# EG_robot.net
KiCad netlist of a schematic drawn in Altium Designer
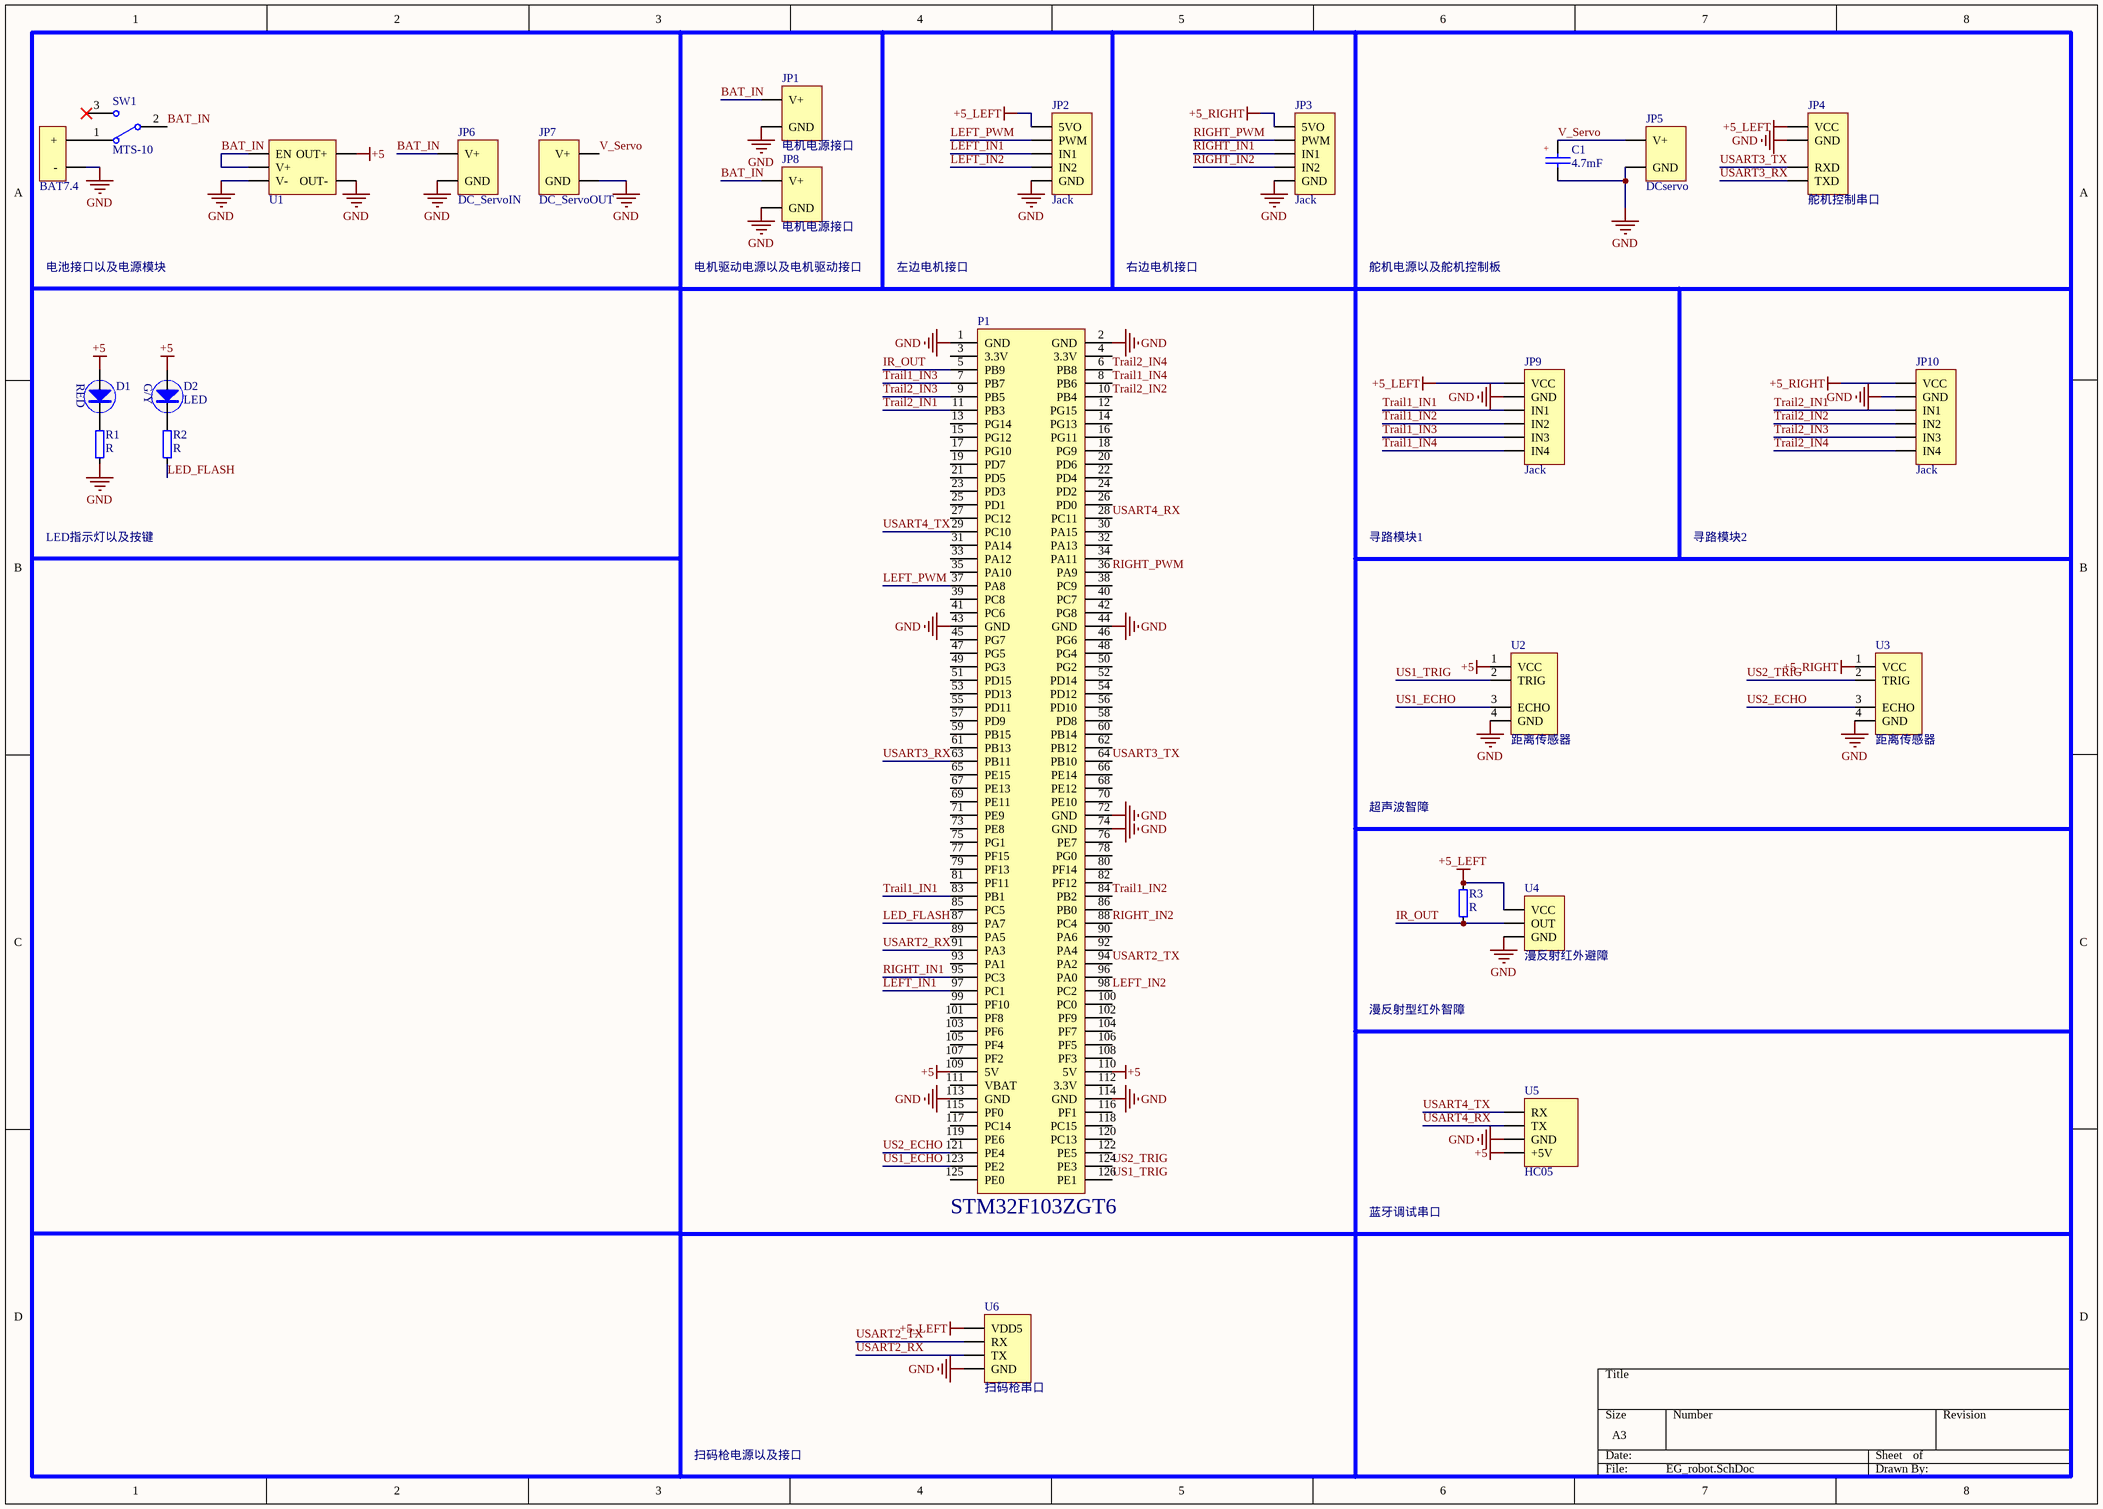
[diagram p0: EG_robot.SchDoc]

(export (version "E")
  (design (tool "Eeschema 10.0.6"))
  (components
    (comp (ref "BAT1") (value "BAT7.4") (footprint "POWER") (libsource (lib "EG_robot") (part "POWER_COM")))
    (comp (ref "C1")
      (value "4.7mF")
      (footprint "CAP 7.5*16*31.5 - BK")
      (description "7.6*16*35")
      (libsource (lib "EG_robot") (part "CAP_DIP7.6*16.35"))
    )
    (comp (ref "D1")
      (value "1206LED")
      (footprint "LED 1206R")
      (description "LED")
      (libsource (lib "EG_robot") (part "LED_RED"))
    )
    (comp (ref "D2") (value "LED") (footprint "LED 1206Y") (libsource (lib "EG_robot") (part "LED_GY")))
    (comp (ref "JP1")
      (value "电机电源接口")
      (footprint "SMALL_POWER_JACK")
      (libsource (lib "EG_robot") (part "DC_moto"))
    )
    (comp (ref "JP2")
      (value "Jack")
      (footprint "XH2.54-LI-5P")
      (description "White Small")
      (libsource (lib "EG_robot") (part "Moto"))
    )
    (comp (ref "JP3")
      (value "Jack")
      (footprint "XH2.54-LI-5P")
      (description "White Small")
      (libsource (lib "EG_robot") (part "Moto"))
    )
    (comp (ref "JP4")
      (value "舵机控制串口")
      (footprint "XH2.54-LI-4P")
      (libsource (lib "EG_robot") (part "舵机控制串口"))
    )
    (comp (ref "JP5")
      (value "DCservo")
      (footprint "SMALL_POWER_JACK")
      (description "Power input for Servo Control Board")
      (libsource (lib "EG_robot") (part "DCservo"))
    )
    (comp (ref "JP6")
      (value "DC_ServoIN")
      (footprint "SMALL_POWER_JACK")
      (libsource (lib "EG_robot") (part "DC_ServoIN"))
    )
    (comp (ref "JP7")
      (value "DC_ServoOUT")
      (footprint "SMALL_POWER_JACK")
      (libsource (lib "EG_robot") (part "DC_ServoOUT"))
    )
    (comp (ref "JP8")
      (value "电机电源接口")
      (footprint "SMALL_POWER_JACK")
      (libsource (lib "EG_robot") (part "DC_moto"))
    )
    (comp (ref "JP9")
      (value "Jack")
      (footprint "XH2.54-LI-6P")
      (description "White Small")
      (libsource (lib "EG_robot") (part "循迹模块"))
    )
    (comp (ref "JP10")
      (value "Jack")
      (footprint "XH2.54-LI-6P")
      (description "White Small")
      (libsource (lib "EG_robot") (part "循迹模块"))
    )
    (comp (ref "P1")
      (value "Header 63X2")
      (footprint "YD最小系统版接口")
      (description "Header, 126-Pin, Dual row")
      (fields (field (name "PUBLISHER") "Altium Limited"))
      (libsource (lib "EG_robot") (part "Header 63X2"))
    )
    (comp (ref "R1")
      (value "R")
      (footprint "1206R")
      (description "SMT_1206")
      (libsource (lib "EG_robot") (part "SMT1206"))
    )
    (comp (ref "R2")
      (value "R")
      (footprint "1206R")
      (description "SMT_1206")
      (libsource (lib "EG_robot") (part "SMT1206"))
    )
    (comp (ref "R3")
      (value "R")
      (footprint "1206R")
      (description "SMT_1206")
      (libsource (lib "EG_robot") (part "SMT1206"))
    )
    (comp (ref "SW1")
      (value "MTS-10")
      (footprint "MTS-10x")
      (description "MTS-10 series")
      (libsource (lib "EG_robot") (part "MTS_10-DIP"))
    )
    (comp (ref "U1")
      (value "DC5V")
      (footprint "DC5V_BUCKBOOST")
      (description "DC5V Fixed Buck-Boost voltage regulator")
      (libsource (lib "EG_robot") (part "DC5V"))
    )
    (comp (ref "U2")
      (value "距离传感器")
      (footprint "XH2.54-LI-4P")
      (description "Ultrasonic distant detector")
      (libsource (lib "EG_robot") (part "HCSR04"))
    )
    (comp (ref "U3")
      (value "距离传感器")
      (footprint "XH2.54-LI-4P")
      (description "Ultrasonic distant detector")
      (libsource (lib "EG_robot") (part "HCSR04"))
    )
    (comp (ref "U4") (value "漫反射红外避障") (footprint "XH2.54-LI-3P") (libsource (lib "EG_robot") (part "红外避障")))
    (comp (ref "U5") (value "HC05") (footprint "XH2.54-LI-4P") (libsource (lib "EG_robot") (part "HC05")))
    (comp (ref "U6") (value "扫码枪串口") (footprint "XH2.54-LI-4P") (libsource (lib "EG_robot") (part "扫码枪")))
  )
  (nets
    (net (code "1") (name "+5") (class "Default")
      (node (ref "D1") (pin "1") (pinfunction "A_1") (pintype "passive"))
      (node (ref "D2") (pin "1") (pinfunction "A_1") (pintype "passive"))
      (node (ref "P1") (pin "109") (pinfunction "5V_109") (pintype "passive"))
      (node (ref "P1") (pin "110") (pinfunction "5V_110") (pintype "passive"))
      (node (ref "U1") (pin "2") (pinfunction "OUT+_2") (pintype "passive"))
      (node (ref "U2") (pin "1") (pinfunction "VCC_1") (pintype "passive"))
      (node (ref "U5") (pin "4") (pinfunction "+5V_4") (pintype "passive"))
    )
    (net (code "2") (name "+5_LEFT") (class "Default")
      (node (ref "JP2") (pin "1") (pinfunction "5VO_1") (pintype "passive"))
      (node (ref "JP4") (pin "1") (pinfunction "VCC_1") (pintype "passive"))
      (node (ref "JP9") (pin "1") (pinfunction "VCC_1") (pintype "passive"))
      (node (ref "R3") (pin "2") (pinfunction "2_2") (pintype "passive"))
      (node (ref "U4") (pin "1") (pinfunction "VCC_1") (pintype "passive"))
      (node (ref "U6") (pin "1") (pinfunction "VDD5_1") (pintype "passive"))
    )
    (net (code "3") (name "+5_RIGHT") (class "Default")
      (node (ref "JP10") (pin "1") (pinfunction "VCC_1") (pintype "passive"))
      (node (ref "JP3") (pin "1") (pinfunction "5VO_1") (pintype "passive"))
      (node (ref "U3") (pin "1") (pinfunction "VCC_1") (pintype "passive"))
    )
    (net (code "4") (name "/BAT_IN") (class "Default")
      (node (ref "JP1") (pin "1") (pinfunction "V+_1") (pintype "passive"))
      (node (ref "JP6") (pin "1") (pinfunction "V+_1") (pintype "passive"))
      (node (ref "JP8") (pin "1") (pinfunction "V+_1") (pintype "passive"))
      (node (ref "SW1") (pin "2") (pinfunction "2_2") (pintype "passive"))
      (node (ref "U1") (pin "3") (pinfunction "EN_3") (pintype "passive"))
      (node (ref "U1") (pin "4") (pinfunction "V+_4") (pintype "passive"))
    )
    (net (code "5") (name "/IR_OUT") (class "Default")
      (node (ref "P1") (pin "5") (pinfunction "PB9_5") (pintype "passive"))
      (node (ref "R3") (pin "1") (pinfunction "1_1") (pintype "passive"))
      (node (ref "U4") (pin "2") (pinfunction "OUT_2") (pintype "passive"))
    )
    (net (code "6") (name "/LED_FLASH") (class "Default")
      (node (ref "P1") (pin "87") (pinfunction "PA7_87") (pintype "passive"))
      (node (ref "R2") (pin "1") (pinfunction "1_1") (pintype "passive"))
    )
    (net (code "7") (name "/LEFT_IN1") (class "Default")
      (node (ref "JP2") (pin "3") (pinfunction "IN1_3") (pintype "passive"))
      (node (ref "P1") (pin "97") (pinfunction "PC1_97") (pintype "passive"))
    )
    (net (code "8") (name "/LEFT_IN2") (class "Default")
      (node (ref "JP2") (pin "4") (pinfunction "IN2_4") (pintype "passive"))
      (node (ref "P1") (pin "98") (pinfunction "PC2_98") (pintype "passive"))
    )
    (net (code "9") (name "/LEFT_PWM") (class "Default")
      (node (ref "JP2") (pin "2") (pinfunction "PWM_2") (pintype "passive"))
      (node (ref "P1") (pin "37") (pinfunction "PA8_37") (pintype "passive"))
    )
    (net (code "10") (name "/RIGHT_IN1") (class "Default")
      (node (ref "JP3") (pin "3") (pinfunction "IN1_3") (pintype "passive"))
      (node (ref "P1") (pin "95") (pinfunction "PC3_95") (pintype "passive"))
    )
    (net (code "11") (name "/RIGHT_IN2") (class "Default")
      (node (ref "JP3") (pin "4") (pinfunction "IN2_4") (pintype "passive"))
      (node (ref "P1") (pin "88") (pinfunction "PC4_88") (pintype "passive"))
    )
    (net (code "12") (name "/RIGHT_PWM") (class "Default")
      (node (ref "JP3") (pin "2") (pinfunction "PWM_2") (pintype "passive"))
      (node (ref "P1") (pin "36") (pinfunction "PA9_36") (pintype "passive"))
    )
    (net (code "13") (name "/Trail1_IN1") (class "Default")
      (node (ref "JP9") (pin "3") (pinfunction "IN1_3") (pintype "passive"))
      (node (ref "P1") (pin "83") (pinfunction "PB1_83") (pintype "passive"))
    )
    (net (code "14") (name "/Trail1_IN2") (class "Default")
      (node (ref "JP9") (pin "4") (pinfunction "IN2_4") (pintype "passive"))
      (node (ref "P1") (pin "84") (pinfunction "PB2_84") (pintype "passive"))
    )
    (net (code "15") (name "/Trail1_IN3") (class "Default")
      (node (ref "JP9") (pin "5") (pinfunction "IN3_5") (pintype "passive"))
      (node (ref "P1") (pin "7") (pinfunction "PB7_7") (pintype "passive"))
    )
    (net (code "16") (name "/Trail1_IN4") (class "Default")
      (node (ref "JP9") (pin "6") (pinfunction "IN4_6") (pintype "passive"))
      (node (ref "P1") (pin "8") (pinfunction "PB6_8") (pintype "passive"))
    )
    (net (code "17") (name "/Trail2_IN1") (class "Default")
      (node (ref "JP10") (pin "3") (pinfunction "IN1_3") (pintype "passive"))
      (node (ref "P1") (pin "11") (pinfunction "PB3_11") (pintype "passive"))
    )
    (net (code "18") (name "/Trail2_IN2") (class "Default")
      (node (ref "JP10") (pin "4") (pinfunction "IN2_4") (pintype "passive"))
      (node (ref "P1") (pin "10") (pinfunction "PB4_10") (pintype "passive"))
    )
    (net (code "19") (name "/Trail2_IN3") (class "Default")
      (node (ref "JP10") (pin "5") (pinfunction "IN3_5") (pintype "passive"))
      (node (ref "P1") (pin "9") (pinfunction "PB5_9") (pintype "passive"))
    )
    (net (code "20") (name "/Trail2_IN4") (class "Default")
      (node (ref "JP10") (pin "6") (pinfunction "IN4_6") (pintype "passive"))
      (node (ref "P1") (pin "6") (pinfunction "PB8_6") (pintype "passive"))
    )
    (net (code "21") (name "/US1_ECHO") (class "Default")
      (node (ref "P1") (pin "123") (pinfunction "PE2_123") (pintype "passive"))
      (node (ref "U2") (pin "3") (pinfunction "ECHO_3") (pintype "passive"))
    )
    (net (code "22") (name "/US1_TRIG") (class "Default")
      (node (ref "P1") (pin "126") (pinfunction "PE1_126") (pintype "passive"))
      (node (ref "U2") (pin "2") (pinfunction "TRIG_2") (pintype "passive"))
    )
    (net (code "23") (name "/US2_ECHO") (class "Default")
      (node (ref "P1") (pin "121") (pinfunction "PE4_121") (pintype "passive"))
      (node (ref "U3") (pin "3") (pinfunction "ECHO_3") (pintype "passive"))
    )
    (net (code "24") (name "/US2_TRIG") (class "Default")
      (node (ref "P1") (pin "124") (pinfunction "PE3_124") (pintype "passive"))
      (node (ref "U3") (pin "2") (pinfunction "TRIG_2") (pintype "passive"))
    )
    (net (code "25") (name "/USART2_RX") (class "Default")
      (node (ref "P1") (pin "91") (pinfunction "PA3_91") (pintype "passive"))
      (node (ref "U6") (pin "3") (pinfunction "TX_3") (pintype "passive"))
    )
    (net (code "26") (name "/USART2_TX") (class "Default")
      (node (ref "P1") (pin "94") (pinfunction "PA2_94") (pintype "passive"))
      (node (ref "U6") (pin "2") (pinfunction "RX_2") (pintype "passive"))
    )
    (net (code "27") (name "/USART3_RX") (class "Default")
      (node (ref "JP4") (pin "4") (pinfunction "TXD_4") (pintype "passive"))
      (node (ref "P1") (pin "63") (pinfunction "PB11_63") (pintype "passive"))
    )
    (net (code "28") (name "/USART3_TX") (class "Default")
      (node (ref "JP4") (pin "3") (pinfunction "RXD_3") (pintype "passive"))
      (node (ref "P1") (pin "64") (pinfunction "PB10_64") (pintype "passive"))
    )
    (net (code "29") (name "/USART4_RX") (class "Default")
      (node (ref "P1") (pin "28") (pinfunction "PC11_28") (pintype "passive"))
      (node (ref "U5") (pin "2") (pinfunction "TX_2") (pintype "passive"))
    )
    (net (code "30") (name "/USART4_TX") (class "Default")
      (node (ref "P1") (pin "29") (pinfunction "PC10_29") (pintype "passive"))
      (node (ref "U5") (pin "1") (pinfunction "RX_1") (pintype "passive"))
    )
    (net (code "31") (name "/V_Servo") (class "Default")
      (node (ref "C1") (pin "1") (pinfunction "1_1") (pintype "passive"))
      (node (ref "JP5") (pin "1") (pinfunction "V+_1") (pintype "passive"))
      (node (ref "JP7") (pin "1") (pinfunction "V+_1") (pintype "passive"))
    )
    (net (code "32") (name "GND") (class "Default")
      (node (ref "BAT1") (pin "2") (pinfunction "-_2") (pintype "passive"))
      (node (ref "C1") (pin "2") (pinfunction "2_2") (pintype "passive"))
      (node (ref "JP1") (pin "2") (pinfunction "GND_2") (pintype "passive"))
      (node (ref "JP10") (pin "2") (pinfunction "GND_2") (pintype "passive"))
      (node (ref "JP2") (pin "5") (pinfunction "GND_5") (pintype "passive"))
      (node (ref "JP3") (pin "5") (pinfunction "GND_5") (pintype "passive"))
      (node (ref "JP4") (pin "2") (pinfunction "GND_2") (pintype "passive"))
      (node (ref "JP5") (pin "2") (pinfunction "GND_2") (pintype "passive"))
      (node (ref "JP6") (pin "2") (pinfunction "GND_2") (pintype "passive"))
      (node (ref "JP7") (pin "2") (pinfunction "GND_2") (pintype "passive"))
      (node (ref "JP8") (pin "2") (pinfunction "GND_2") (pintype "passive"))
      (node (ref "JP9") (pin "2") (pinfunction "GND_2") (pintype "passive"))
      (node (ref "P1") (pin "1") (pinfunction "GND_1") (pintype "passive"))
      (node (ref "P1") (pin "113") (pinfunction "GND_113") (pintype "passive"))
      (node (ref "P1") (pin "114") (pinfunction "GND_114") (pintype "passive"))
      (node (ref "P1") (pin "2") (pinfunction "GND_2") (pintype "passive"))
      (node (ref "P1") (pin "43") (pinfunction "GND_43") (pintype "passive"))
      (node (ref "P1") (pin "44") (pinfunction "GND_44") (pintype "passive"))
      (node (ref "P1") (pin "72") (pinfunction "GND_72") (pintype "passive"))
      (node (ref "P1") (pin "74") (pinfunction "GND_74") (pintype "passive"))
      (node (ref "R1") (pin "1") (pinfunction "1_1") (pintype "passive"))
      (node (ref "U1") (pin "1") (pinfunction "OUT-_1") (pintype "passive"))
      (node (ref "U1") (pin "5") (pinfunction "V-_5") (pintype "passive"))
      (node (ref "U2") (pin "4") (pinfunction "GND_4") (pintype "passive"))
      (node (ref "U3") (pin "4") (pinfunction "GND_4") (pintype "passive"))
      (node (ref "U4") (pin "3") (pinfunction "GND_3") (pintype "passive"))
      (node (ref "U5") (pin "3") (pinfunction "GND_3") (pintype "passive"))
      (node (ref "U6") (pin "4") (pinfunction "GND_4") (pintype "passive"))
    )
    (net (code "33") (name "Net-(BAT1-+)") (class "Default")
      (node (ref "BAT1") (pin "1") (pinfunction "+_1") (pintype "passive"))
      (node (ref "SW1") (pin "1") (pinfunction "1_1") (pintype "passive"))
    )
    (net (code "34") (name "Net-(D1-K)") (class "Default")
      (node (ref "D1") (pin "2") (pinfunction "K_2") (pintype "passive"))
      (node (ref "R1") (pin "2") (pinfunction "2_2") (pintype "passive"))
    )
    (net (code "35") (name "Net-(D2-K)") (class "Default")
      (node (ref "D2") (pin "2") (pinfunction "K_2") (pintype "passive"))
      (node (ref "R2") (pin "2") (pinfunction "2_2") (pintype "passive"))
    )
    (net (code "36") (name "unconnected-(P1-3.3V-Pad3)") (class "Default")
      (node (ref "P1") (pin "3") (pinfunction "3.3V_3") (pintype "passive"))
    )
    (net (code "37") (name "unconnected-(P1-3.3V-Pad4)") (class "Default")
      (node (ref "P1") (pin "4") (pinfunction "3.3V_4") (pintype "passive"))
    )
    (net (code "38") (name "unconnected-(P1-3.3V-Pad112)") (class "Default")
      (node (ref "P1") (pin "112") (pinfunction "3.3V_112") (pintype "passive"))
    )
    (net (code "39") (name "unconnected-(P1-PA0-Pad96)") (class "Default")
      (node (ref "P1") (pin "96") (pinfunction "PA0_96") (pintype "passive"))
    )
    (net (code "40") (name "unconnected-(P1-PA1-Pad93)") (class "Default")
      (node (ref "P1") (pin "93") (pinfunction "PA1_93") (pintype "passive"))
    )
    (net (code "41") (name "unconnected-(P1-PA4-Pad92)") (class "Default")
      (node (ref "P1") (pin "92") (pinfunction "PA4_92") (pintype "passive"))
    )
    (net (code "42") (name "unconnected-(P1-PA5-Pad89)") (class "Default")
      (node (ref "P1") (pin "89") (pinfunction "PA5_89") (pintype "passive"))
    )
    (net (code "43") (name "unconnected-(P1-PA6-Pad90)") (class "Default")
      (node (ref "P1") (pin "90") (pinfunction "PA6_90") (pintype "passive"))
    )
    (net (code "44") (name "unconnected-(P1-PA10-Pad35)") (class "Default")
      (node (ref "P1") (pin "35") (pinfunction "PA10_35") (pintype "passive"))
    )
    (net (code "45") (name "unconnected-(P1-PA11-Pad34)") (class "Default")
      (node (ref "P1") (pin "34") (pinfunction "PA11_34") (pintype "passive"))
    )
    (net (code "46") (name "unconnected-(P1-PA12-Pad33)") (class "Default")
      (node (ref "P1") (pin "33") (pinfunction "PA12_33") (pintype "passive"))
    )
    (net (code "47") (name "unconnected-(P1-PA13-Pad32)") (class "Default")
      (node (ref "P1") (pin "32") (pinfunction "PA13_32") (pintype "passive"))
    )
    (net (code "48") (name "unconnected-(P1-PA14-Pad31)") (class "Default")
      (node (ref "P1") (pin "31") (pinfunction "PA14_31") (pintype "passive"))
    )
    (net (code "49") (name "unconnected-(P1-PA15-Pad30)") (class "Default")
      (node (ref "P1") (pin "30") (pinfunction "PA15_30") (pintype "passive"))
    )
    (net (code "50") (name "unconnected-(P1-PB0-Pad86)") (class "Default")
      (node (ref "P1") (pin "86") (pinfunction "PB0_86") (pintype "passive"))
    )
    (net (code "51") (name "unconnected-(P1-PB12-Pad62)") (class "Default")
      (node (ref "P1") (pin "62") (pinfunction "PB12_62") (pintype "passive"))
    )
    (net (code "52") (name "unconnected-(P1-PB13-Pad61)") (class "Default")
      (node (ref "P1") (pin "61") (pinfunction "PB13_61") (pintype "passive"))
    )
    (net (code "53") (name "unconnected-(P1-PB14-Pad60)") (class "Default")
      (node (ref "P1") (pin "60") (pinfunction "PB14_60") (pintype "passive"))
    )
    (net (code "54") (name "unconnected-(P1-PB15-Pad59)") (class "Default")
      (node (ref "P1") (pin "59") (pinfunction "PB15_59") (pintype "passive"))
    )
    (net (code "55") (name "unconnected-(P1-PC0-Pad100)") (class "Default")
      (node (ref "P1") (pin "100") (pinfunction "PC0_100") (pintype "passive"))
    )
    (net (code "56") (name "unconnected-(P1-PC5-Pad85)") (class "Default")
      (node (ref "P1") (pin "85") (pinfunction "PC5_85") (pintype "passive"))
    )
    (net (code "57") (name "unconnected-(P1-PC6-Pad41)") (class "Default")
      (node (ref "P1") (pin "41") (pinfunction "PC6_41") (pintype "passive"))
    )
    (net (code "58") (name "unconnected-(P1-PC7-Pad40)") (class "Default")
      (node (ref "P1") (pin "40") (pinfunction "PC7_40") (pintype "passive"))
    )
    (net (code "59") (name "unconnected-(P1-PC8-Pad39)") (class "Default")
      (node (ref "P1") (pin "39") (pinfunction "PC8_39") (pintype "passive"))
    )
    (net (code "60") (name "unconnected-(P1-PC9-Pad38)") (class "Default")
      (node (ref "P1") (pin "38") (pinfunction "PC9_38") (pintype "passive"))
    )
    (net (code "61") (name "unconnected-(P1-PC12-Pad27)") (class "Default")
      (node (ref "P1") (pin "27") (pinfunction "PC12_27") (pintype "passive"))
    )
    (net (code "62") (name "unconnected-(P1-PC13-Pad120)") (class "Default")
      (node (ref "P1") (pin "120") (pinfunction "PC13_120") (pintype "passive"))
    )
    (net (code "63") (name "unconnected-(P1-PC14-Pad117)") (class "Default")
      (node (ref "P1") (pin "117") (pinfunction "PC14_117") (pintype "passive"))
    )
    (net (code "64") (name "unconnected-(P1-PC15-Pad118)") (class "Default")
      (node (ref "P1") (pin "118") (pinfunction "PC15_118") (pintype "passive"))
    )
    (net (code "65") (name "unconnected-(P1-PD0-Pad26)") (class "Default")
      (node (ref "P1") (pin "26") (pinfunction "PD0_26") (pintype "passive"))
    )
    (net (code "66") (name "unconnected-(P1-PD1-Pad25)") (class "Default")
      (node (ref "P1") (pin "25") (pinfunction "PD1_25") (pintype "passive"))
    )
    (net (code "67") (name "unconnected-(P1-PD2-Pad24)") (class "Default")
      (node (ref "P1") (pin "24") (pinfunction "PD2_24") (pintype "passive"))
    )
    (net (code "68") (name "unconnected-(P1-PD3-Pad23)") (class "Default")
      (node (ref "P1") (pin "23") (pinfunction "PD3_23") (pintype "passive"))
    )
    (net (code "69") (name "unconnected-(P1-PD4-Pad22)") (class "Default")
      (node (ref "P1") (pin "22") (pinfunction "PD4_22") (pintype "passive"))
    )
    (net (code "70") (name "unconnected-(P1-PD5-Pad21)") (class "Default")
      (node (ref "P1") (pin "21") (pinfunction "PD5_21") (pintype "passive"))
    )
    (net (code "71") (name "unconnected-(P1-PD6-Pad20)") (class "Default")
      (node (ref "P1") (pin "20") (pinfunction "PD6_20") (pintype "passive"))
    )
    (net (code "72") (name "unconnected-(P1-PD7-Pad19)") (class "Default")
      (node (ref "P1") (pin "19") (pinfunction "PD7_19") (pintype "passive"))
    )
    (net (code "73") (name "unconnected-(P1-PD8-Pad58)") (class "Default")
      (node (ref "P1") (pin "58") (pinfunction "PD8_58") (pintype "passive"))
    )
    (net (code "74") (name "unconnected-(P1-PD9-Pad57)") (class "Default")
      (node (ref "P1") (pin "57") (pinfunction "PD9_57") (pintype "passive"))
    )
    (net (code "75") (name "unconnected-(P1-PD10-Pad56)") (class "Default")
      (node (ref "P1") (pin "56") (pinfunction "PD10_56") (pintype "passive"))
    )
    (net (code "76") (name "unconnected-(P1-PD11-Pad55)") (class "Default")
      (node (ref "P1") (pin "55") (pinfunction "PD11_55") (pintype "passive"))
    )
    (net (code "77") (name "unconnected-(P1-PD12-Pad54)") (class "Default")
      (node (ref "P1") (pin "54") (pinfunction "PD12_54") (pintype "passive"))
    )
    (net (code "78") (name "unconnected-(P1-PD13-Pad53)") (class "Default")
      (node (ref "P1") (pin "53") (pinfunction "PD13_53") (pintype "passive"))
    )
    (net (code "79") (name "unconnected-(P1-PD14-Pad52)") (class "Default")
      (node (ref "P1") (pin "52") (pinfunction "PD14_52") (pintype "passive"))
    )
    (net (code "80") (name "unconnected-(P1-PD15-Pad51)") (class "Default")
      (node (ref "P1") (pin "51") (pinfunction "PD15_51") (pintype "passive"))
    )
    (net (code "81") (name "unconnected-(P1-PE0-Pad125)") (class "Default")
      (node (ref "P1") (pin "125") (pinfunction "PE0_125") (pintype "passive"))
    )
    (net (code "82") (name "unconnected-(P1-PE5-Pad122)") (class "Default")
      (node (ref "P1") (pin "122") (pinfunction "PE5_122") (pintype "passive"))
    )
    (net (code "83") (name "unconnected-(P1-PE6-Pad119)") (class "Default")
      (node (ref "P1") (pin "119") (pinfunction "PE6_119") (pintype "passive"))
    )
    (net (code "84") (name "unconnected-(P1-PE7-Pad76)") (class "Default")
      (node (ref "P1") (pin "76") (pinfunction "PE7_76") (pintype "passive"))
    )
    (net (code "85") (name "unconnected-(P1-PE8-Pad73)") (class "Default")
      (node (ref "P1") (pin "73") (pinfunction "PE8_73") (pintype "passive"))
    )
    (net (code "86") (name "unconnected-(P1-PE9-Pad71)") (class "Default")
      (node (ref "P1") (pin "71") (pinfunction "PE9_71") (pintype "passive"))
    )
    (net (code "87") (name "unconnected-(P1-PE10-Pad70)") (class "Default")
      (node (ref "P1") (pin "70") (pinfunction "PE10_70") (pintype "passive"))
    )
    (net (code "88") (name "unconnected-(P1-PE11-Pad69)") (class "Default")
      (node (ref "P1") (pin "69") (pinfunction "PE11_69") (pintype "passive"))
    )
    (net (code "89") (name "unconnected-(P1-PE12-Pad68)") (class "Default")
      (node (ref "P1") (pin "68") (pinfunction "PE12_68") (pintype "passive"))
    )
    (net (code "90") (name "unconnected-(P1-PE13-Pad67)") (class "Default")
      (node (ref "P1") (pin "67") (pinfunction "PE13_67") (pintype "passive"))
    )
    (net (code "91") (name "unconnected-(P1-PE14-Pad66)") (class "Default")
      (node (ref "P1") (pin "66") (pinfunction "PE14_66") (pintype "passive"))
    )
    (net (code "92") (name "unconnected-(P1-PE15-Pad65)") (class "Default")
      (node (ref "P1") (pin "65") (pinfunction "PE15_65") (pintype "passive"))
    )
    (net (code "93") (name "unconnected-(P1-PF0-Pad115)") (class "Default")
      (node (ref "P1") (pin "115") (pinfunction "PF0_115") (pintype "passive"))
    )
    (net (code "94") (name "unconnected-(P1-PF1-Pad116)") (class "Default")
      (node (ref "P1") (pin "116") (pinfunction "PF1_116") (pintype "passive"))
    )
    (net (code "95") (name "unconnected-(P1-PF2-Pad107)") (class "Default")
      (node (ref "P1") (pin "107") (pinfunction "PF2_107") (pintype "passive"))
    )
    (net (code "96") (name "unconnected-(P1-PF3-Pad108)") (class "Default")
      (node (ref "P1") (pin "108") (pinfunction "PF3_108") (pintype "passive"))
    )
    (net (code "97") (name "unconnected-(P1-PF4-Pad105)") (class "Default")
      (node (ref "P1") (pin "105") (pinfunction "PF4_105") (pintype "passive"))
    )
    (net (code "98") (name "unconnected-(P1-PF5-Pad106)") (class "Default")
      (node (ref "P1") (pin "106") (pinfunction "PF5_106") (pintype "passive"))
    )
    (net (code "99") (name "unconnected-(P1-PF6-Pad103)") (class "Default")
      (node (ref "P1") (pin "103") (pinfunction "PF6_103") (pintype "passive"))
    )
    (net (code "100") (name "unconnected-(P1-PF7-Pad104)") (class "Default")
      (node (ref "P1") (pin "104") (pinfunction "PF7_104") (pintype "passive"))
    )
    (net (code "101") (name "unconnected-(P1-PF8-Pad101)") (class "Default")
      (node (ref "P1") (pin "101") (pinfunction "PF8_101") (pintype "passive"))
    )
    (net (code "102") (name "unconnected-(P1-PF9-Pad102)") (class "Default")
      (node (ref "P1") (pin "102") (pinfunction "PF9_102") (pintype "passive"))
    )
    (net (code "103") (name "unconnected-(P1-PF10-Pad99)") (class "Default")
      (node (ref "P1") (pin "99") (pinfunction "PF10_99") (pintype "passive"))
    )
    (net (code "104") (name "unconnected-(P1-PF11-Pad81)") (class "Default")
      (node (ref "P1") (pin "81") (pinfunction "PF11_81") (pintype "passive"))
    )
    (net (code "105") (name "unconnected-(P1-PF12-Pad82)") (class "Default")
      (node (ref "P1") (pin "82") (pinfunction "PF12_82") (pintype "passive"))
    )
    (net (code "106") (name "unconnected-(P1-PF13-Pad79)") (class "Default")
      (node (ref "P1") (pin "79") (pinfunction "PF13_79") (pintype "passive"))
    )
    (net (code "107") (name "unconnected-(P1-PF14-Pad80)") (class "Default")
      (node (ref "P1") (pin "80") (pinfunction "PF14_80") (pintype "passive"))
    )
    (net (code "108") (name "unconnected-(P1-PF15-Pad77)") (class "Default")
      (node (ref "P1") (pin "77") (pinfunction "PF15_77") (pintype "passive"))
    )
    (net (code "109") (name "unconnected-(P1-PG0-Pad78)") (class "Default")
      (node (ref "P1") (pin "78") (pinfunction "PG0_78") (pintype "passive"))
    )
    (net (code "110") (name "unconnected-(P1-PG1-Pad75)") (class "Default")
      (node (ref "P1") (pin "75") (pinfunction "PG1_75") (pintype "passive"))
    )
    (net (code "111") (name "unconnected-(P1-PG2-Pad50)") (class "Default")
      (node (ref "P1") (pin "50") (pinfunction "PG2_50") (pintype "passive"))
    )
    (net (code "112") (name "unconnected-(P1-PG3-Pad49)") (class "Default")
      (node (ref "P1") (pin "49") (pinfunction "PG3_49") (pintype "passive"))
    )
    (net (code "113") (name "unconnected-(P1-PG4-Pad48)") (class "Default")
      (node (ref "P1") (pin "48") (pinfunction "PG4_48") (pintype "passive"))
    )
    (net (code "114") (name "unconnected-(P1-PG5-Pad47)") (class "Default")
      (node (ref "P1") (pin "47") (pinfunction "PG5_47") (pintype "passive"))
    )
    (net (code "115") (name "unconnected-(P1-PG6-Pad46)") (class "Default")
      (node (ref "P1") (pin "46") (pinfunction "PG6_46") (pintype "passive"))
    )
    (net (code "116") (name "unconnected-(P1-PG7-Pad45)") (class "Default")
      (node (ref "P1") (pin "45") (pinfunction "PG7_45") (pintype "passive"))
    )
    (net (code "117") (name "unconnected-(P1-PG8-Pad42)") (class "Default")
      (node (ref "P1") (pin "42") (pinfunction "PG8_42") (pintype "passive"))
    )
    (net (code "118") (name "unconnected-(P1-PG9-Pad18)") (class "Default")
      (node (ref "P1") (pin "18") (pinfunction "PG9_18") (pintype "passive"))
    )
    (net (code "119") (name "unconnected-(P1-PG10-Pad17)") (class "Default")
      (node (ref "P1") (pin "17") (pinfunction "PG10_17") (pintype "passive"))
    )
    (net (code "120") (name "unconnected-(P1-PG11-Pad16)") (class "Default")
      (node (ref "P1") (pin "16") (pinfunction "PG11_16") (pintype "passive"))
    )
    (net (code "121") (name "unconnected-(P1-PG12-Pad15)") (class "Default")
      (node (ref "P1") (pin "15") (pinfunction "PG12_15") (pintype "passive"))
    )
    (net (code "122") (name "unconnected-(P1-PG13-Pad14)") (class "Default")
      (node (ref "P1") (pin "14") (pinfunction "PG13_14") (pintype "passive"))
    )
    (net (code "123") (name "unconnected-(P1-PG14-Pad13)") (class "Default")
      (node (ref "P1") (pin "13") (pinfunction "PG14_13") (pintype "passive"))
    )
    (net (code "124") (name "unconnected-(P1-PG15-Pad12)") (class "Default")
      (node (ref "P1") (pin "12") (pinfunction "PG15_12") (pintype "passive"))
    )
    (net (code "125") (name "unconnected-(P1-VBAT-Pad111)") (class "Default")
      (node (ref "P1") (pin "111") (pinfunction "VBAT_111") (pintype "passive"))
    )
    (net (code "126") (name "unconnected-(SW1-Pad3)") (class "Default")
      (node (ref "SW1") (pin "3") (pinfunction "3_3") (pintype "passive+no_connect"))
    )
  )
)
